# supply_L5973.net
KiCad netlist of a schematic drawn in EAGLE
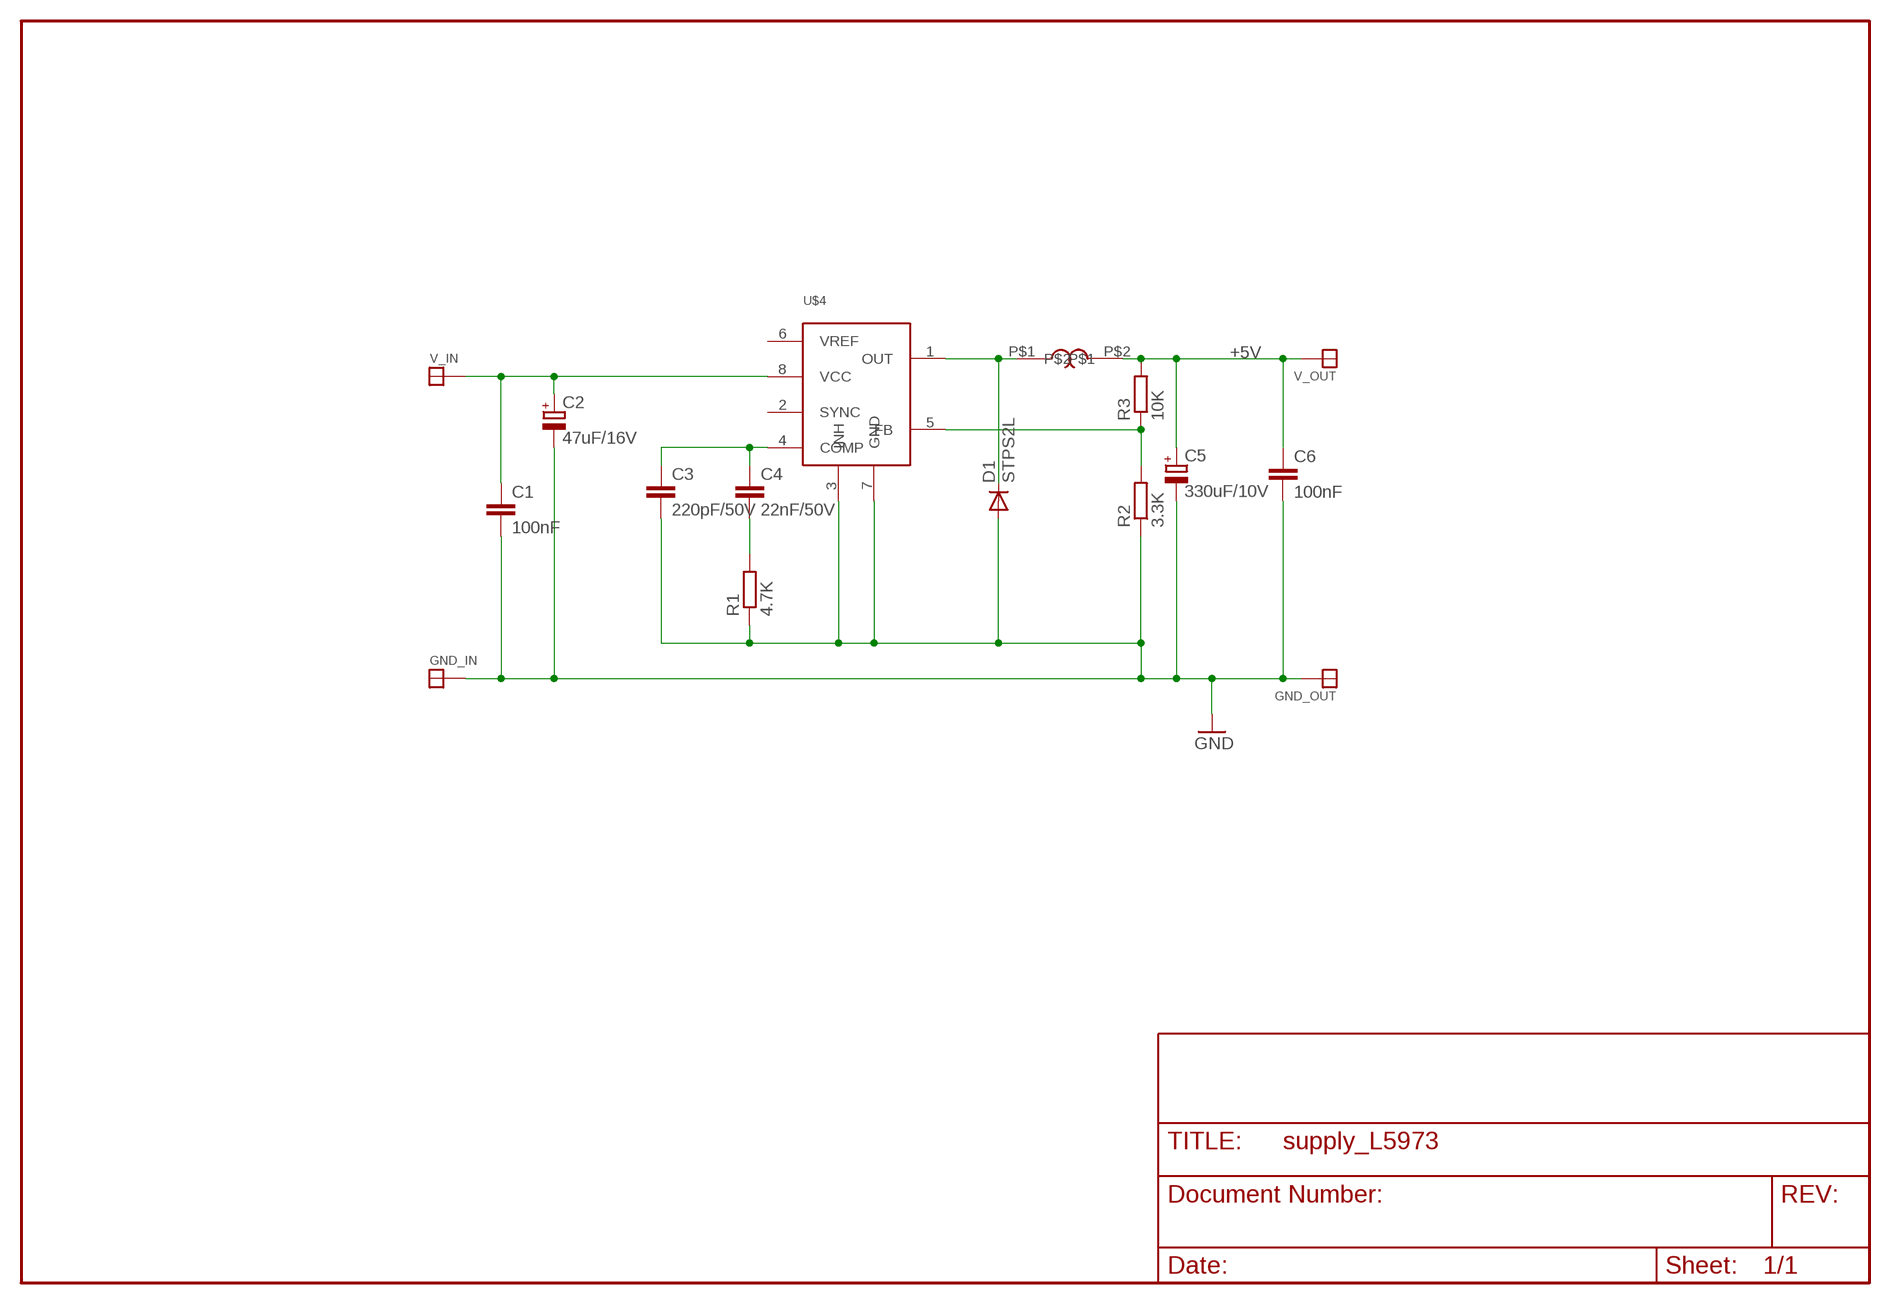
[diagram p0: schematic, sheet 1]

(export (version "E")
  (design (tool "Eeschema 10.0.6"))
  (components
    (comp (ref "C1")
      (value "100nF")
      (footprint "eagle-import:C0603")
      (libsource (lib "eagle-import") (part "C-EUC0603"))
    )
    (comp (ref "C2")
      (value "47uF/16V")
      (footprint "eagle-import:D_7343-31R")
      (libsource (lib "eagle-import") (part "CPOL-EUD/7343-31R"))
    )
    (comp (ref "C3")
      (value "220pF/50V")
      (footprint "eagle-import:C1206K")
      (libsource (lib "eagle-import") (part "C-EUC1206K"))
    )
    (comp (ref "C4")
      (value "22nF/50V")
      (footprint "eagle-import:C1206K")
      (libsource (lib "eagle-import") (part "C-EUC1206K"))
    )
    (comp (ref "C5")
      (value "330uF/10V")
      (footprint "eagle-import:D_7343-31R")
      (libsource (lib "eagle-import") (part "CPOL-EUD/7343-31R"))
    )
    (comp (ref "C6")
      (value "100nF")
      (footprint "eagle-import:C0603")
      (libsource (lib "eagle-import") (part "C-EUC0603"))
    )
    (comp (ref "D1")
      (value "STPS2L")
      (footprint "eagle-import:SMA")
      (libsource (lib "eagle-import") (part "STPS2L"))
    )
    (comp (ref "GND_IN")
      (value "SOLDER_PAD100_50")
      (footprint "eagle-import:SOLDER_PAD_100_50")
      (libsource (lib "eagle-import") (part "SOLDER_PAD100_50"))
    )
    (comp (ref "GND_OUT")
      (value "SOLDER_PAD100_50")
      (footprint "eagle-import:SOLDER_PAD_100_50")
      (libsource (lib "eagle-import") (part "SOLDER_PAD100_50"))
    )
    (comp (ref "L1")
      (value "15uH")
      (footprint "eagle-import:WE_PD")
      (libsource (lib "eagle-import") (part "WE_PD"))
    )
    (comp (ref "R1")
      (value "4.7K")
      (footprint "eagle-import:R0603")
      (libsource (lib "eagle-import") (part "R-EU_R0603"))
    )
    (comp (ref "R2")
      (value "3.3K")
      (footprint "eagle-import:R0603")
      (libsource (lib "eagle-import") (part "R-EU_R0603"))
    )
    (comp (ref "R3")
      (value "10K")
      (footprint "eagle-import:R0603")
      (libsource (lib "eagle-import") (part "R-EU_R0603"))
    )
    (comp (ref "U$4")
      (value "L5973D")
      (footprint "eagle-import:SO08")
      (libsource (lib "eagle-import") (part "L5973D"))
    )
    (comp (ref "V_IN")
      (value "SOLDER_PAD100_50")
      (footprint "eagle-import:SOLDER_PAD_100_50")
      (libsource (lib "eagle-import") (part "SOLDER_PAD100_50"))
    )
    (comp (ref "V_OUT")
      (value "SOLDER_PAD100_50")
      (footprint "eagle-import:SOLDER_PAD_100_50")
      (libsource (lib "eagle-import") (part "SOLDER_PAD100_50"))
    )
  )
  (nets
    (net (code "1") (name "/+5V") (class "Default")
      (node (ref "C5") (pin "+") (pinfunction "+_+") (pintype "passive"))
      (node (ref "C6") (pin "1") (pinfunction "1_1") (pintype "passive"))
      (node (ref "L1") (pin "P$2") (pinfunction "P$2_P$2") (pintype "bidirectional"))
      (node (ref "R3") (pin "2") (pinfunction "2_2") (pintype "passive"))
      (node (ref "V_OUT") (pin "P$1") (pinfunction "P$1_P$1") (pintype "bidirectional"))
    )
    (net (code "2") (name "GND") (class "Default")
      (node (ref "C1") (pin "2") (pinfunction "2_2") (pintype "passive"))
      (node (ref "C2") (pin "-") (pinfunction "-_-") (pintype "passive"))
      (node (ref "C3") (pin "2") (pinfunction "2_2") (pintype "passive"))
      (node (ref "C5") (pin "-") (pinfunction "-_-") (pintype "passive"))
      (node (ref "C6") (pin "2") (pinfunction "2_2") (pintype "passive"))
      (node (ref "D1") (pin "P$1") (pinfunction "A_P$1") (pintype "passive"))
      (node (ref "GND_IN") (pin "P$1") (pinfunction "P$1_P$1") (pintype "bidirectional"))
      (node (ref "GND_OUT") (pin "P$1") (pinfunction "P$1_P$1") (pintype "bidirectional"))
      (node (ref "R1") (pin "1") (pinfunction "1_1") (pintype "passive"))
      (node (ref "R2") (pin "1") (pinfunction "1_1") (pintype "passive"))
      (node (ref "U$4") (pin "3") (pinfunction "INH_3") (pintype "bidirectional"))
      (node (ref "U$4") (pin "7") (pinfunction "GND_7") (pintype "bidirectional"))
    )
    (net (code "3") (name "Net-(C4-Pad2)") (class "Default")
      (node (ref "C4") (pin "2") (pinfunction "2_2") (pintype "passive"))
      (node (ref "R1") (pin "2") (pinfunction "2_2") (pintype "passive"))
    )
    (net (code "4") (name "Net-(D1-C)") (class "Default")
      (node (ref "D1") (pin "P$2") (pinfunction "C_P$2") (pintype "passive"))
      (node (ref "L1") (pin "P$1") (pinfunction "P$1_P$1") (pintype "bidirectional"))
      (node (ref "U$4") (pin "1") (pinfunction "OUT_1") (pintype "bidirectional"))
    )
    (net (code "5") (name "Net-(U$4-COMP)") (class "Default")
      (node (ref "C3") (pin "1") (pinfunction "1_1") (pintype "passive"))
      (node (ref "C4") (pin "1") (pinfunction "1_1") (pintype "passive"))
      (node (ref "U$4") (pin "4") (pinfunction "COMP_4") (pintype "bidirectional"))
    )
    (net (code "6") (name "Net-(U$4-FB)") (class "Default")
      (node (ref "R2") (pin "2") (pinfunction "2_2") (pintype "passive"))
      (node (ref "R3") (pin "1") (pinfunction "1_1") (pintype "passive"))
      (node (ref "U$4") (pin "5") (pinfunction "FB_5") (pintype "bidirectional"))
    )
    (net (code "7") (name "Net-(U$4-VCC)") (class "Default")
      (node (ref "C1") (pin "1") (pinfunction "1_1") (pintype "passive"))
      (node (ref "C2") (pin "+") (pinfunction "+_+") (pintype "passive"))
      (node (ref "U$4") (pin "8") (pinfunction "VCC_8") (pintype "bidirectional"))
      (node (ref "V_IN") (pin "P$1") (pinfunction "P$1_P$1") (pintype "bidirectional"))
    )
    (net (code "8") (name "unconnected-(U$4-SYNC-Pad2)") (class "Default")
      (node (ref "U$4") (pin "2") (pinfunction "SYNC_2") (pintype "bidirectional"))
    )
    (net (code "9") (name "unconnected-(U$4-VREF-Pad6)") (class "Default")
      (node (ref "U$4") (pin "6") (pinfunction "VREF_6") (pintype "bidirectional"))
    )
  )
)
